# Arduino_Shield.net
KiCad netlist of a schematic drawn in EAGLE
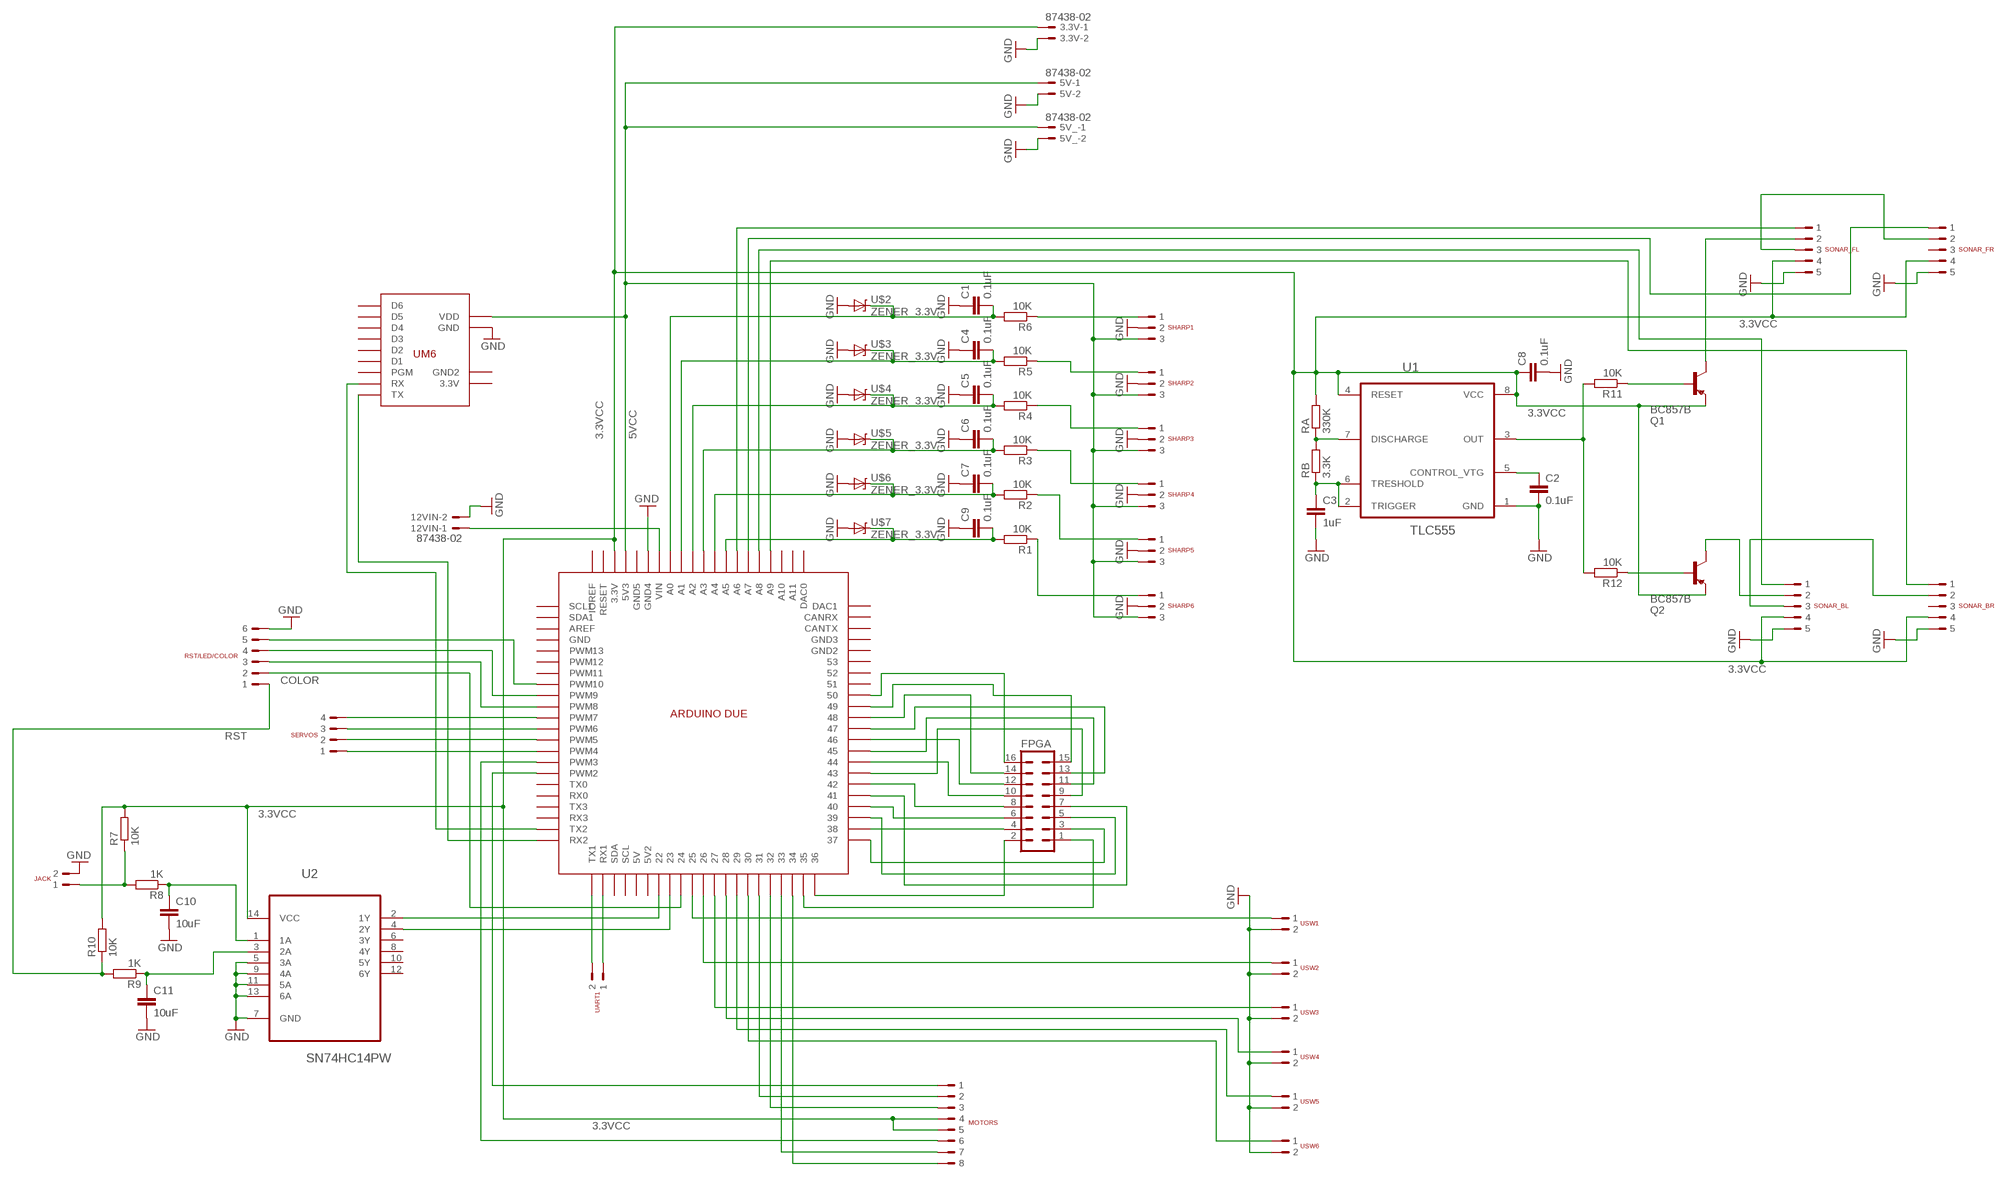
[diagram p0: schematic, sheet 1]

(export (version "E")
  (design (tool "Eeschema 10.0.6"))
  (components
    (comp (ref "3.3V")
      (value "87438-02")
      (footprint "eagle-import:87438-02")
      (libsource (lib "eagle-import") (part "87438-02"))
    )
    (comp (ref "5V")
      (value "87438-02")
      (footprint "eagle-import:87438-02")
      (libsource (lib "eagle-import") (part "87438-02"))
    )
    (comp (ref "5V_")
      (value "87438-02")
      (footprint "eagle-import:87438-02")
      (libsource (lib "eagle-import") (part "87438-02"))
    )
    (comp (ref "12VIN")
      (value "87438-02")
      (footprint "eagle-import:87438-02")
      (libsource (lib "eagle-import") (part "87438-02"))
    )
    (comp (ref "C1")
      (value "0.1uF")
      (footprint "eagle-import:C0603")
      (libsource (lib "eagle-import") (part "C-EUC0603"))
    )
    (comp (ref "C2")
      (value "0.1uF")
      (footprint "eagle-import:C0603")
      (libsource (lib "eagle-import") (part "C-EUC0603"))
    )
    (comp (ref "C3")
      (value "1uF")
      (footprint "eagle-import:C0603")
      (libsource (lib "eagle-import") (part "C-EUC0603"))
    )
    (comp (ref "C4")
      (value "0.1uF")
      (footprint "eagle-import:C0603")
      (libsource (lib "eagle-import") (part "C-EUC0603"))
    )
    (comp (ref "C5")
      (value "0.1uF")
      (footprint "eagle-import:C0603")
      (libsource (lib "eagle-import") (part "C-EUC0603"))
    )
    (comp (ref "C6")
      (value "0.1uF")
      (footprint "eagle-import:C0603")
      (libsource (lib "eagle-import") (part "C-EUC0603"))
    )
    (comp (ref "C7")
      (value "0.1uF")
      (footprint "eagle-import:C0603")
      (libsource (lib "eagle-import") (part "C-EUC0603"))
    )
    (comp (ref "C8")
      (value "0.1uF")
      (footprint "eagle-import:C0603")
      (libsource (lib "eagle-import") (part "C-EUC0603"))
    )
    (comp (ref "C9")
      (value "0.1uF")
      (footprint "eagle-import:C0603")
      (libsource (lib "eagle-import") (part "C-EUC0603"))
    )
    (comp (ref "C10")
      (value "10uF")
      (footprint "eagle-import:C0603")
      (libsource (lib "eagle-import") (part "C-EUC0603"))
    )
    (comp (ref "C11")
      (value "10uF")
      (footprint "eagle-import:C0603")
      (libsource (lib "eagle-import") (part "C-EUC0603"))
    )
    (comp (ref "FPGA")
      (value "ML16")
      (footprint "eagle-import:ML16")
      (libsource (lib "eagle-import") (part "ML16"))
    )
    (comp (ref "JACK")
      (value "87437-0243")
      (footprint "eagle-import:87437-0243")
      (libsource (lib "eagle-import") (part "87437-0243"))
    )
    (comp (ref "MOTORS")
      (value "87437-0843")
      (footprint "eagle-import:87437-0843")
      (libsource (lib "eagle-import") (part "87437-0843"))
    )
    (comp (ref "Q1")
      (value "BC857B")
      (footprint "eagle-import:SOT23")
      (libsource (lib "eagle-import") (part "-?SOT23MMBTA56"))
    )
    (comp (ref "Q2")
      (value "BC857B")
      (footprint "eagle-import:SOT23")
      (libsource (lib "eagle-import") (part "-?SOT23MMBTA56"))
    )
    (comp (ref "R1")
      (value "10K")
      (footprint "eagle-import:R0603")
      (libsource (lib "eagle-import") (part "R-EU_R0603"))
    )
    (comp (ref "R2")
      (value "10K")
      (footprint "eagle-import:R0603")
      (libsource (lib "eagle-import") (part "R-EU_R0603"))
    )
    (comp (ref "R3")
      (value "10K")
      (footprint "eagle-import:R0603")
      (libsource (lib "eagle-import") (part "R-EU_R0603"))
    )
    (comp (ref "R4")
      (value "10K")
      (footprint "eagle-import:R0603")
      (libsource (lib "eagle-import") (part "R-EU_R0603"))
    )
    (comp (ref "R5")
      (value "10K")
      (footprint "eagle-import:R0603")
      (libsource (lib "eagle-import") (part "R-EU_R0603"))
    )
    (comp (ref "R6")
      (value "10K")
      (footprint "eagle-import:R0603")
      (libsource (lib "eagle-import") (part "R-EU_R0603"))
    )
    (comp (ref "R7")
      (value "10K")
      (footprint "eagle-import:R0603")
      (libsource (lib "eagle-import") (part "R-EU_R0603"))
    )
    (comp (ref "R8")
      (value "1K")
      (footprint "eagle-import:R0603")
      (libsource (lib "eagle-import") (part "R-EU_R0603"))
    )
    (comp (ref "R9")
      (value "1K")
      (footprint "eagle-import:R0603")
      (libsource (lib "eagle-import") (part "R-EU_R0603"))
    )
    (comp (ref "R10")
      (value "10K")
      (footprint "eagle-import:R0603")
      (libsource (lib "eagle-import") (part "R-EU_R0603"))
    )
    (comp (ref "R11")
      (value "10K")
      (footprint "eagle-import:R0603")
      (libsource (lib "eagle-import") (part "R-EU_R0603"))
    )
    (comp (ref "R12")
      (value "10K")
      (footprint "eagle-import:R0603")
      (libsource (lib "eagle-import") (part "R-EU_R0603"))
    )
    (comp (ref "RA")
      (value "330K")
      (footprint "eagle-import:R0603")
      (libsource (lib "eagle-import") (part "R-EU_R0603"))
    )
    (comp (ref "RB")
      (value "3.3K")
      (footprint "eagle-import:R0603")
      (libsource (lib "eagle-import") (part "R-EU_R0603"))
    )
    (comp (ref "RST/LED/COLOR")
      (value "87437-0643")
      (footprint "eagle-import:87437-0643")
      (libsource (lib "eagle-import") (part "87437-0643"))
    )
    (comp (ref "SERVOS")
      (value "87437-0443")
      (footprint "eagle-import:87437-0443")
      (libsource (lib "eagle-import") (part "87437-0443"))
    )
    (comp (ref "SHARP1")
      (value "87437-0343")
      (footprint "eagle-import:87437-0343")
      (libsource (lib "eagle-import") (part "87437-0343"))
    )
    (comp (ref "SHARP2")
      (value "87437-0343")
      (footprint "eagle-import:87437-0343")
      (libsource (lib "eagle-import") (part "87437-0343"))
    )
    (comp (ref "SHARP3")
      (value "87437-0343")
      (footprint "eagle-import:87437-0343")
      (libsource (lib "eagle-import") (part "87437-0343"))
    )
    (comp (ref "SHARP4")
      (value "87437-0343")
      (footprint "eagle-import:87437-0343")
      (libsource (lib "eagle-import") (part "87437-0343"))
    )
    (comp (ref "SHARP5")
      (value "87437-0343")
      (footprint "eagle-import:87437-0343")
      (libsource (lib "eagle-import") (part "87437-0343"))
    )
    (comp (ref "SHARP6")
      (value "87437-0343")
      (footprint "eagle-import:87437-0343")
      (libsource (lib "eagle-import") (part "87437-0343"))
    )
    (comp (ref "SONAR_BL")
      (value "87437-0543")
      (footprint "eagle-import:87437-0543")
      (libsource (lib "eagle-import") (part "87437-0543"))
    )
    (comp (ref "SONAR_BR")
      (value "87437-0543")
      (footprint "eagle-import:87437-0543")
      (libsource (lib "eagle-import") (part "87437-0543"))
    )
    (comp (ref "SONAR_FL")
      (value "87437-0543")
      (footprint "eagle-import:87437-0543")
      (libsource (lib "eagle-import") (part "87437-0543"))
    )
    (comp (ref "SONAR_FR")
      (value "87437-0543")
      (footprint "eagle-import:87437-0543")
      (libsource (lib "eagle-import") (part "87437-0543"))
    )
    (comp (ref "U$1")
      (value "ARDUINO-DUE")
      (footprint "eagle-import:ARDUINO-DUE")
      (libsource (lib "eagle-import") (part "ARDUINO-DUE"))
    )
    (comp (ref "U$2")
      (value "ZENER_3.3V")
      (footprint "eagle-import:SOD-323")
      (libsource (lib "eagle-import") (part "DIODE-ZENER-BZT52"))
    )
    (comp (ref "U$3")
      (value "ZENER_3.3V")
      (footprint "eagle-import:SOD-323")
      (libsource (lib "eagle-import") (part "DIODE-ZENER-BZT52"))
    )
    (comp (ref "U$4")
      (value "ZENER_3.3V")
      (footprint "eagle-import:SOD-323")
      (libsource (lib "eagle-import") (part "DIODE-ZENER-BZT52"))
    )
    (comp (ref "U$5")
      (value "ZENER_3.3V")
      (footprint "eagle-import:SOD-323")
      (libsource (lib "eagle-import") (part "DIODE-ZENER-BZT52"))
    )
    (comp (ref "U$6")
      (value "ZENER_3.3V")
      (footprint "eagle-import:SOD-323")
      (libsource (lib "eagle-import") (part "DIODE-ZENER-BZT52"))
    )
    (comp (ref "U$7")
      (value "ZENER_3.3V")
      (footprint "eagle-import:SOD-323")
      (libsource (lib "eagle-import") (part "DIODE-ZENER-BZT52"))
    )
    (comp (ref "U1")
      (value "TLC555")
      (footprint "eagle-import:SOIC127P600X175-8N")
      (fields (field (name "MPN") "LM555CM"))
      (libsource (lib "eagle-import") (part "LM555CM"))
    )
    (comp (ref "U2")
      (value "SN74HC14PW")
      (footprint "eagle-import:SOP65P640X120-14N")
      (libsource (lib "eagle-import") (part "SN74HC14PW"))
    )
    (comp (ref "UART1")
      (value "87437-0243")
      (footprint "eagle-import:87437-0243")
      (libsource (lib "eagle-import") (part "87437-0243"))
    )
    (comp (ref "UM6")
      (value "UM6")
      (footprint "eagle-import:UM6")
      (libsource (lib "eagle-import") (part "UM6"))
    )
    (comp (ref "USW1")
      (value "87437-0243")
      (footprint "eagle-import:87437-0243")
      (libsource (lib "eagle-import") (part "87437-0243"))
    )
    (comp (ref "USW2")
      (value "87437-0243")
      (footprint "eagle-import:87437-0243")
      (libsource (lib "eagle-import") (part "87437-0243"))
    )
    (comp (ref "USW3")
      (value "87437-0243")
      (footprint "eagle-import:87437-0243")
      (libsource (lib "eagle-import") (part "87437-0243"))
    )
    (comp (ref "USW4")
      (value "87437-0243")
      (footprint "eagle-import:87437-0243")
      (libsource (lib "eagle-import") (part "87437-0243"))
    )
    (comp (ref "USW5")
      (value "87437-0243")
      (footprint "eagle-import:87437-0243")
      (libsource (lib "eagle-import") (part "87437-0243"))
    )
    (comp (ref "USW6")
      (value "87437-0243")
      (footprint "eagle-import:87437-0243")
      (libsource (lib "eagle-import") (part "87437-0243"))
    )
  )
  (nets
    (net (code "1") (name "/3.3VCC") (class "Default")
      (node (ref "3.3V") (pin "1") (pinfunction "S_1") (pintype "passive"))
      (node (ref "C8") (pin "1") (pinfunction "1_1") (pintype "passive"))
      (node (ref "MOTORS") (pin "P$4") (pinfunction "4_P$4") (pintype "bidirectional"))
      (node (ref "MOTORS") (pin "P$5") (pinfunction "5_P$5") (pintype "bidirectional"))
      (node (ref "Q1") (pin "2") (pinfunction "E_2") (pintype "passive"))
      (node (ref "Q2") (pin "2") (pinfunction "E_2") (pintype "passive"))
      (node (ref "R10") (pin "2") (pinfunction "2_2") (pintype "passive"))
      (node (ref "R7") (pin "2") (pinfunction "2_2") (pintype "passive"))
      (node (ref "RA") (pin "2") (pinfunction "2_2") (pintype "passive"))
      (node (ref "SONAR_BL") (pin "P$4") (pinfunction "4_P$4") (pintype "bidirectional"))
      (node (ref "SONAR_BR") (pin "P$4") (pinfunction "4_P$4") (pintype "bidirectional"))
      (node (ref "SONAR_FL") (pin "P$4") (pinfunction "4_P$4") (pintype "bidirectional"))
      (node (ref "SONAR_FR") (pin "P$4") (pinfunction "4_P$4") (pintype "bidirectional"))
      (node (ref "U$1") (pin "3.3V") (pinfunction "3.3V_3.3V") (pintype "bidirectional"))
      (node (ref "U1") (pin "4") (pinfunction "RESET_4") (pintype "input"))
      (node (ref "U1") (pin "8") (pinfunction "VCC_8") (pintype "power_in"))
      (node (ref "U2") (pin "14") (pinfunction "VCC_14") (pintype "power_in"))
    )
    (net (code "2") (name "/5VCC") (class "Default")
      (node (ref "5V") (pin "1") (pinfunction "S_1") (pintype "passive"))
      (node (ref "5V_") (pin "1") (pinfunction "S_1") (pintype "passive"))
      (node (ref "SHARP1") (pin "P$3") (pinfunction "3_P$3") (pintype "bidirectional"))
      (node (ref "SHARP2") (pin "P$3") (pinfunction "3_P$3") (pintype "bidirectional"))
      (node (ref "SHARP3") (pin "P$3") (pinfunction "3_P$3") (pintype "bidirectional"))
      (node (ref "SHARP4") (pin "P$3") (pinfunction "3_P$3") (pintype "bidirectional"))
      (node (ref "SHARP5") (pin "P$3") (pinfunction "3_P$3") (pintype "bidirectional"))
      (node (ref "SHARP6") (pin "P$3") (pinfunction "3_P$3") (pintype "bidirectional"))
      (node (ref "U$1") (pin "5V3") (pinfunction "5V3_5V3") (pintype "bidirectional"))
      (node (ref "UM6") (pin "P$10") (pinfunction "VDD_P$10") (pintype "bidirectional"))
    )
    (net (code "3") (name "/COLOR") (class "Default")
      (node (ref "RST/LED/COLOR") (pin "P$2") (pinfunction "2_P$2") (pintype "bidirectional"))
      (node (ref "U$1") (pin "24") (pinfunction "24_24") (pintype "bidirectional"))
    )
    (net (code "4") (name "/RST") (class "Default")
      (node (ref "R10") (pin "1") (pinfunction "1_1") (pintype "passive"))
      (node (ref "R9") (pin "2") (pinfunction "2_2") (pintype "passive"))
      (node (ref "RST/LED/COLOR") (pin "P$1") (pinfunction "1_P$1") (pintype "bidirectional"))
    )
    (net (code "5") (name "GND") (class "Default")
      (node (ref "12VIN") (pin "2") (pinfunction "S_2") (pintype "passive"))
      (node (ref "3.3V") (pin "2") (pinfunction "S_2") (pintype "passive"))
      (node (ref "5V") (pin "2") (pinfunction "S_2") (pintype "passive"))
      (node (ref "5V_") (pin "2") (pinfunction "S_2") (pintype "passive"))
      (node (ref "C1") (pin "1") (pinfunction "1_1") (pintype "passive"))
      (node (ref "C10") (pin "2") (pinfunction "2_2") (pintype "passive"))
      (node (ref "C11") (pin "2") (pinfunction "2_2") (pintype "passive"))
      (node (ref "C2") (pin "2") (pinfunction "2_2") (pintype "passive"))
      (node (ref "C3") (pin "2") (pinfunction "2_2") (pintype "passive"))
      (node (ref "C4") (pin "1") (pinfunction "1_1") (pintype "passive"))
      (node (ref "C5") (pin "1") (pinfunction "1_1") (pintype "passive"))
      (node (ref "C6") (pin "1") (pinfunction "1_1") (pintype "passive"))
      (node (ref "C7") (pin "1") (pinfunction "1_1") (pintype "passive"))
      (node (ref "C8") (pin "2") (pinfunction "2_2") (pintype "passive"))
      (node (ref "C9") (pin "1") (pinfunction "1_1") (pintype "passive"))
      (node (ref "JACK") (pin "P$2") (pinfunction "2_P$2") (pintype "bidirectional"))
      (node (ref "RST/LED/COLOR") (pin "P$6") (pinfunction "6_P$6") (pintype "bidirectional"))
      (node (ref "SHARP1") (pin "P$2") (pinfunction "2_P$2") (pintype "bidirectional"))
      (node (ref "SHARP2") (pin "P$2") (pinfunction "2_P$2") (pintype "bidirectional"))
      (node (ref "SHARP3") (pin "P$2") (pinfunction "2_P$2") (pintype "bidirectional"))
      (node (ref "SHARP4") (pin "P$2") (pinfunction "2_P$2") (pintype "bidirectional"))
      (node (ref "SHARP5") (pin "P$2") (pinfunction "2_P$2") (pintype "bidirectional"))
      (node (ref "SHARP6") (pin "P$2") (pinfunction "2_P$2") (pintype "bidirectional"))
      (node (ref "SONAR_BL") (pin "P$5") (pinfunction "5_P$5") (pintype "bidirectional"))
      (node (ref "SONAR_BR") (pin "P$5") (pinfunction "5_P$5") (pintype "bidirectional"))
      (node (ref "SONAR_FL") (pin "P$5") (pinfunction "5_P$5") (pintype "bidirectional"))
      (node (ref "SONAR_FR") (pin "P$5") (pinfunction "5_P$5") (pintype "bidirectional"))
      (node (ref "U$1") (pin "GND4") (pinfunction "GND4_GND4") (pintype "bidirectional"))
      (node (ref "U$2") (pin "2") (pinfunction "A_2") (pintype "passive"))
      (node (ref "U$3") (pin "2") (pinfunction "A_2") (pintype "passive"))
      (node (ref "U$4") (pin "2") (pinfunction "A_2") (pintype "passive"))
      (node (ref "U$5") (pin "2") (pinfunction "A_2") (pintype "passive"))
      (node (ref "U$6") (pin "2") (pinfunction "A_2") (pintype "passive"))
      (node (ref "U$7") (pin "2") (pinfunction "A_2") (pintype "passive"))
      (node (ref "U1") (pin "1") (pinfunction "GND_1") (pintype "passive"))
      (node (ref "U2") (pin "11") (pinfunction "5A_11") (pintype "input"))
      (node (ref "U2") (pin "13") (pinfunction "6A_13") (pintype "input"))
      (node (ref "U2") (pin "5") (pinfunction "3A_5") (pintype "input"))
      (node (ref "U2") (pin "7") (pinfunction "GND_7") (pintype "passive"))
      (node (ref "U2") (pin "9") (pinfunction "4A_9") (pintype "input"))
      (node (ref "UM6") (pin "P$11") (pinfunction "GND_P$11") (pintype "bidirectional"))
      (node (ref "USW1") (pin "P$2") (pinfunction "2_P$2") (pintype "bidirectional"))
      (node (ref "USW2") (pin "P$2") (pinfunction "2_P$2") (pintype "bidirectional"))
      (node (ref "USW3") (pin "P$2") (pinfunction "2_P$2") (pintype "bidirectional"))
      (node (ref "USW4") (pin "P$2") (pinfunction "2_P$2") (pintype "bidirectional"))
      (node (ref "USW5") (pin "P$2") (pinfunction "2_P$2") (pintype "bidirectional"))
      (node (ref "USW6") (pin "P$2") (pinfunction "2_P$2") (pintype "bidirectional"))
    )
    (net (code "6") (name "Net-(12VINA-S)") (class "Default")
      (node (ref "12VIN") (pin "1") (pinfunction "S_1") (pintype "passive"))
      (node (ref "U$1") (pin "VIN") (pinfunction "VIN_VIN") (pintype "bidirectional"))
    )
    (net (code "7") (name "Net-(FPGA-Pad1)") (class "Default")
      (node (ref "FPGA") (pin "1") (pinfunction "1_1") (pintype "passive"))
      (node (ref "U$1") (pin "35") (pinfunction "35_35") (pintype "bidirectional"))
    )
    (net (code "8") (name "Net-(FPGA-Pad2)") (class "Default")
      (node (ref "FPGA") (pin "2") (pinfunction "2_2") (pintype "passive"))
      (node (ref "U$1") (pin "36") (pinfunction "36_36") (pintype "bidirectional"))
    )
    (net (code "9") (name "Net-(FPGA-Pad3)") (class "Default")
      (node (ref "FPGA") (pin "3") (pinfunction "3_3") (pintype "passive"))
      (node (ref "U$1") (pin "37") (pinfunction "37_37") (pintype "bidirectional"))
    )
    (net (code "10") (name "Net-(FPGA-Pad4)") (class "Default")
      (node (ref "FPGA") (pin "4") (pinfunction "4_4") (pintype "passive"))
      (node (ref "U$1") (pin "38") (pinfunction "38_38") (pintype "bidirectional"))
    )
    (net (code "11") (name "Net-(FPGA-Pad5)") (class "Default")
      (node (ref "FPGA") (pin "5") (pinfunction "5_5") (pintype "passive"))
      (node (ref "U$1") (pin "39") (pinfunction "39_39") (pintype "bidirectional"))
    )
    (net (code "12") (name "Net-(FPGA-Pad6)") (class "Default")
      (node (ref "FPGA") (pin "6") (pinfunction "6_6") (pintype "passive"))
      (node (ref "U$1") (pin "40") (pinfunction "40_40") (pintype "bidirectional"))
    )
    (net (code "13") (name "Net-(FPGA-Pad7)") (class "Default")
      (node (ref "FPGA") (pin "7") (pinfunction "7_7") (pintype "passive"))
      (node (ref "U$1") (pin "41") (pinfunction "41_41") (pintype "bidirectional"))
    )
    (net (code "14") (name "Net-(FPGA-Pad8)") (class "Default")
      (node (ref "FPGA") (pin "8") (pinfunction "8_8") (pintype "passive"))
      (node (ref "U$1") (pin "42") (pinfunction "42_42") (pintype "bidirectional"))
    )
    (net (code "15") (name "Net-(FPGA-Pad9)") (class "Default")
      (node (ref "FPGA") (pin "9") (pinfunction "9_9") (pintype "passive"))
      (node (ref "U$1") (pin "43") (pinfunction "43_43") (pintype "bidirectional"))
    )
    (net (code "16") (name "Net-(FPGA-Pad10)") (class "Default")
      (node (ref "FPGA") (pin "10") (pinfunction "10_10") (pintype "passive"))
      (node (ref "U$1") (pin "44") (pinfunction "44_44") (pintype "bidirectional"))
    )
    (net (code "17") (name "Net-(FPGA-Pad11)") (class "Default")
      (node (ref "FPGA") (pin "11") (pinfunction "11_11") (pintype "passive"))
      (node (ref "U$1") (pin "45") (pinfunction "45_45") (pintype "bidirectional"))
    )
    (net (code "18") (name "Net-(FPGA-Pad12)") (class "Default")
      (node (ref "FPGA") (pin "12") (pinfunction "12_12") (pintype "passive"))
      (node (ref "U$1") (pin "46") (pinfunction "46_46") (pintype "bidirectional"))
    )
    (net (code "19") (name "Net-(FPGA-Pad13)") (class "Default")
      (node (ref "FPGA") (pin "13") (pinfunction "13_13") (pintype "passive"))
      (node (ref "U$1") (pin "47") (pinfunction "47_47") (pintype "bidirectional"))
    )
    (net (code "20") (name "Net-(FPGA-Pad14)") (class "Default")
      (node (ref "FPGA") (pin "14") (pinfunction "14_14") (pintype "passive"))
      (node (ref "U$1") (pin "48") (pinfunction "48_48") (pintype "bidirectional"))
    )
    (net (code "21") (name "Net-(FPGA-Pad15)") (class "Default")
      (node (ref "FPGA") (pin "15") (pinfunction "15_15") (pintype "passive"))
      (node (ref "U$1") (pin "49") (pinfunction "49_49") (pintype "bidirectional"))
    )
    (net (code "22") (name "Net-(FPGA-Pad16)") (class "Default")
      (node (ref "FPGA") (pin "16") (pinfunction "16_16") (pintype "passive"))
      (node (ref "U$1") (pin "50") (pinfunction "50_50") (pintype "bidirectional"))
    )
    (net (code "23") (name "Net-(JACK-1)") (class "Default")
      (node (ref "JACK") (pin "P$1") (pinfunction "1_P$1") (pintype "bidirectional"))
      (node (ref "R7") (pin "1") (pinfunction "1_1") (pintype "passive"))
      (node (ref "R8") (pin "2") (pinfunction "2_2") (pintype "passive"))
    )
    (net (code "24") (name "Net-(MOTORS-1)") (class "Default")
      (node (ref "MOTORS") (pin "P$1") (pinfunction "1_P$1") (pintype "bidirectional"))
      (node (ref "U$1") (pin "PWM2") (pinfunction "PWM2_PWM2") (pintype "bidirectional"))
    )
    (net (code "25") (name "Net-(MOTORS-2)") (class "Default")
      (node (ref "MOTORS") (pin "P$2") (pinfunction "2_P$2") (pintype "bidirectional"))
      (node (ref "U$1") (pin "31") (pinfunction "31_31") (pintype "bidirectional"))
    )
    (net (code "26") (name "Net-(MOTORS-3)") (class "Default")
      (node (ref "MOTORS") (pin "P$3") (pinfunction "3_P$3") (pintype "bidirectional"))
      (node (ref "U$1") (pin "32") (pinfunction "32_32") (pintype "bidirectional"))
    )
    (net (code "27") (name "Net-(MOTORS-6)") (class "Default")
      (node (ref "MOTORS") (pin "P$6") (pinfunction "6_P$6") (pintype "bidirectional"))
      (node (ref "U$1") (pin "PWM3") (pinfunction "PWM3_PWM3") (pintype "bidirectional"))
    )
    (net (code "28") (name "Net-(MOTORS-7)") (class "Default")
      (node (ref "MOTORS") (pin "P$7") (pinfunction "7_P$7") (pintype "bidirectional"))
      (node (ref "U$1") (pin "33") (pinfunction "33_33") (pintype "bidirectional"))
    )
    (net (code "29") (name "Net-(MOTORS-8)") (class "Default")
      (node (ref "MOTORS") (pin "P$8") (pinfunction "8_P$8") (pintype "bidirectional"))
      (node (ref "U$1") (pin "34") (pinfunction "34_34") (pintype "bidirectional"))
    )
    (net (code "30") (name "Net-(Q1-B)") (class "Default")
      (node (ref "Q1") (pin "1") (pinfunction "B_1") (pintype "passive"))
      (node (ref "R11") (pin "1") (pinfunction "1_1") (pintype "passive"))
    )
    (net (code "31") (name "Net-(Q1-C)") (class "Default")
      (node (ref "Q1") (pin "3") (pinfunction "C_3") (pintype "passive"))
      (node (ref "SONAR_FL") (pin "P$2") (pinfunction "2_P$2") (pintype "bidirectional"))
    )
    (net (code "32") (name "Net-(Q2-B)") (class "Default")
      (node (ref "Q2") (pin "1") (pinfunction "B_1") (pintype "passive"))
      (node (ref "R12") (pin "1") (pinfunction "1_1") (pintype "passive"))
    )
    (net (code "33") (name "Net-(Q2-C)") (class "Default")
      (node (ref "Q2") (pin "3") (pinfunction "C_3") (pintype "passive"))
      (node (ref "SONAR_BL") (pin "P$2") (pinfunction "2_P$2") (pintype "bidirectional"))
    )
    (net (code "34") (name "Net-(RST/LED/COLOR-3)") (class "Default")
      (node (ref "RST/LED/COLOR") (pin "P$3") (pinfunction "3_P$3") (pintype "bidirectional"))
      (node (ref "U$1") (pin "PWM8") (pinfunction "PWM8_PWM8") (pintype "bidirectional"))
    )
    (net (code "35") (name "Net-(RST/LED/COLOR-4)") (class "Default")
      (node (ref "RST/LED/COLOR") (pin "P$4") (pinfunction "4_P$4") (pintype "bidirectional"))
      (node (ref "U$1") (pin "PWM9") (pinfunction "PWM9_PWM9") (pintype "bidirectional"))
    )
    (net (code "36") (name "Net-(RST/LED/COLOR-5)") (class "Default")
      (node (ref "RST/LED/COLOR") (pin "P$5") (pinfunction "5_P$5") (pintype "bidirectional"))
      (node (ref "U$1") (pin "PWM10") (pinfunction "PWM10_PWM10") (pintype "bidirectional"))
    )
    (net (code "37") (name "Net-(SERVOS-1)") (class "Default")
      (node (ref "SERVOS") (pin "P$1") (pinfunction "1_P$1") (pintype "bidirectional"))
      (node (ref "U$1") (pin "PWM4") (pinfunction "PWM4_PWM4") (pintype "bidirectional"))
    )
    (net (code "38") (name "Net-(SERVOS-2)") (class "Default")
      (node (ref "SERVOS") (pin "P$2") (pinfunction "2_P$2") (pintype "bidirectional"))
      (node (ref "U$1") (pin "PWM5") (pinfunction "PWM5_PWM5") (pintype "bidirectional"))
    )
    (net (code "39") (name "Net-(SERVOS-3)") (class "Default")
      (node (ref "SERVOS") (pin "P$3") (pinfunction "3_P$3") (pintype "bidirectional"))
      (node (ref "U$1") (pin "PWM6") (pinfunction "PWM6_PWM6") (pintype "bidirectional"))
    )
    (net (code "40") (name "Net-(SERVOS-4)") (class "Default")
      (node (ref "SERVOS") (pin "P$4") (pinfunction "4_P$4") (pintype "bidirectional"))
      (node (ref "U$1") (pin "PWM7") (pinfunction "PWM7_PWM7") (pintype "bidirectional"))
    )
    (net (code "41") (name "Net-(SHARP1-1)") (class "Default")
      (node (ref "R6") (pin "1") (pinfunction "1_1") (pintype "passive"))
      (node (ref "SHARP1") (pin "P$1") (pinfunction "1_P$1") (pintype "bidirectional"))
    )
    (net (code "42") (name "Net-(SHARP2-1)") (class "Default")
      (node (ref "R5") (pin "1") (pinfunction "1_1") (pintype "passive"))
      (node (ref "SHARP2") (pin "P$1") (pinfunction "1_P$1") (pintype "bidirectional"))
    )
    (net (code "43") (name "Net-(SHARP3-1)") (class "Default")
      (node (ref "R4") (pin "1") (pinfunction "1_1") (pintype "passive"))
      (node (ref "SHARP3") (pin "P$1") (pinfunction "1_P$1") (pintype "bidirectional"))
    )
    (net (code "44") (name "Net-(SHARP4-1)") (class "Default")
      (node (ref "R3") (pin "1") (pinfunction "1_1") (pintype "passive"))
      (node (ref "SHARP4") (pin "P$1") (pinfunction "1_P$1") (pintype "bidirectional"))
    )
    (net (code "45") (name "Net-(SHARP5-1)") (class "Default")
      (node (ref "R2") (pin "1") (pinfunction "1_1") (pintype "passive"))
      (node (ref "SHARP5") (pin "P$1") (pinfunction "1_P$1") (pintype "bidirectional"))
    )
    (net (code "46") (name "Net-(SHARP6-1)") (class "Default")
      (node (ref "R1") (pin "1") (pinfunction "1_1") (pintype "passive"))
      (node (ref "SHARP6") (pin "P$1") (pinfunction "1_P$1") (pintype "bidirectional"))
    )
    (net (code "47") (name "Net-(SONAR_BL-1)") (class "Default")
      (node (ref "SONAR_BL") (pin "P$1") (pinfunction "1_P$1") (pintype "bidirectional"))
      (node (ref "U$1") (pin "A8") (pinfunction "A8_A8") (pintype "bidirectional"))
    )
    (net (code "48") (name "Net-(SONAR_BL-3)") (class "Default")
      (node (ref "SONAR_BL") (pin "P$3") (pinfunction "3_P$3") (pintype "bidirectional"))
      (node (ref "SONAR_BR") (pin "P$2") (pinfunction "2_P$2") (pintype "bidirectional"))
    )
    (net (code "49") (name "Net-(SONAR_BR-1)") (class "Default")
      (node (ref "SONAR_BR") (pin "P$1") (pinfunction "1_P$1") (pintype "bidirectional"))
      (node (ref "U$1") (pin "A9") (pinfunction "A9_A9") (pintype "bidirectional"))
    )
    (net (code "50") (name "Net-(SONAR_FL-1)") (class "Default")
      (node (ref "SONAR_FL") (pin "P$1") (pinfunction "1_P$1") (pintype "bidirectional"))
      (node (ref "U$1") (pin "A6") (pinfunction "A6_A6") (pintype "bidirectional"))
    )
    (net (code "51") (name "Net-(SONAR_FL-3)") (class "Default")
      (node (ref "SONAR_FL") (pin "P$3") (pinfunction "3_P$3") (pintype "bidirectional"))
      (node (ref "SONAR_FR") (pin "P$2") (pinfunction "2_P$2") (pintype "bidirectional"))
    )
    (net (code "52") (name "Net-(SONAR_FR-1)") (class "Default")
      (node (ref "SONAR_FR") (pin "P$1") (pinfunction "1_P$1") (pintype "bidirectional"))
      (node (ref "U$1") (pin "A7") (pinfunction "A7_A7") (pintype "bidirectional"))
    )
    (net (code "53") (name "Net-(U$2-C)") (class "Default")
      (node (ref "C1") (pin "2") (pinfunction "2_2") (pintype "passive"))
      (node (ref "R6") (pin "2") (pinfunction "2_2") (pintype "passive"))
      (node (ref "U$1") (pin "A0") (pinfunction "A0_A0") (pintype "bidirectional"))
      (node (ref "U$2") (pin "1") (pinfunction "C_1") (pintype "passive"))
    )
    (net (code "54") (name "Net-(U$3-C)") (class "Default")
      (node (ref "C4") (pin "2") (pinfunction "2_2") (pintype "passive"))
      (node (ref "R5") (pin "2") (pinfunction "2_2") (pintype "passive"))
      (node (ref "U$1") (pin "A1") (pinfunction "A1_A1") (pintype "bidirectional"))
      (node (ref "U$3") (pin "1") (pinfunction "C_1") (pintype "passive"))
    )
    (net (code "55") (name "Net-(U$4-C)") (class "Default")
      (node (ref "C5") (pin "2") (pinfunction "2_2") (pintype "passive"))
      (node (ref "R4") (pin "2") (pinfunction "2_2") (pintype "passive"))
      (node (ref "U$1") (pin "A2") (pinfunction "A2_A2") (pintype "bidirectional"))
      (node (ref "U$4") (pin "1") (pinfunction "C_1") (pintype "passive"))
    )
    (net (code "56") (name "Net-(U$5-C)") (class "Default")
      (node (ref "C6") (pin "2") (pinfunction "2_2") (pintype "passive"))
      (node (ref "R3") (pin "2") (pinfunction "2_2") (pintype "passive"))
      (node (ref "U$1") (pin "A3") (pinfunction "A3_A3") (pintype "bidirectional"))
      (node (ref "U$5") (pin "1") (pinfunction "C_1") (pintype "passive"))
    )
    (net (code "57") (name "Net-(U$6-C)") (class "Default")
      (node (ref "C7") (pin "2") (pinfunction "2_2") (pintype "passive"))
      (node (ref "R2") (pin "2") (pinfunction "2_2") (pintype "passive"))
      (node (ref "U$1") (pin "A4") (pinfunction "A4_A4") (pintype "bidirectional"))
      (node (ref "U$6") (pin "1") (pinfunction "C_1") (pintype "passive"))
    )
    (net (code "58") (name "Net-(U$7-C)") (class "Default")
      (node (ref "C9") (pin "2") (pinfunction "2_2") (pintype "passive"))
      (node (ref "R1") (pin "2") (pinfunction "2_2") (pintype "passive"))
      (node (ref "U$1") (pin "A5") (pinfunction "A5_A5") (pintype "bidirectional"))
      (node (ref "U$7") (pin "1") (pinfunction "C_1") (pintype "passive"))
    )
    (net (code "59") (name "Net-(U1-CONTROL_VTG)") (class "Default")
      (node (ref "C2") (pin "1") (pinfunction "1_1") (pintype "passive"))
      (node (ref "U1") (pin "5") (pinfunction "CONTROL_VTG_5") (pintype "input"))
    )
    (net (code "60") (name "Net-(U1-DISCHARGE)") (class "Default")
      (node (ref "RA") (pin "1") (pinfunction "1_1") (pintype "passive"))
      (node (ref "RB") (pin "2") (pinfunction "2_2") (pintype "passive"))
      (node (ref "U1") (pin "7") (pinfunction "DISCHARGE_7") (pintype "input"))
    )
    (net (code "61") (name "Net-(U1-OUT)") (class "Default")
      (node (ref "R11") (pin "2") (pinfunction "2_2") (pintype "passive"))
      (node (ref "R12") (pin "2") (pinfunction "2_2") (pintype "passive"))
      (node (ref "U1") (pin "3") (pinfunction "OUT_3") (pintype "output"))
    )
    (net (code "62") (name "Net-(U1-TRESHOLD)") (class "Default")
      (node (ref "C3") (pin "1") (pinfunction "1_1") (pintype "passive"))
      (node (ref "RB") (pin "1") (pinfunction "1_1") (pintype "passive"))
      (node (ref "U1") (pin "2") (pinfunction "TRIGGER_2") (pintype "input"))
      (node (ref "U1") (pin "6") (pinfunction "TRESHOLD_6") (pintype "input"))
    )
    (net (code "63") (name "Net-(U2-1A)") (class "Default")
      (node (ref "C10") (pin "1") (pinfunction "1_1") (pintype "passive"))
      (node (ref "R8") (pin "1") (pinfunction "1_1") (pintype "passive"))
      (node (ref "U2") (pin "1") (pinfunction "1A_1") (pintype "input"))
    )
    (net (code "64") (name "Net-(U2-1Y)") (class "Default")
      (node (ref "U$1") (pin "22") (pinfunction "22_22") (pintype "bidirectional"))
      (node (ref "U2") (pin "2") (pinfunction "1Y_2") (pintype "output"))
    )
    (net (code "65") (name "Net-(U2-2A)") (class "Default")
      (node (ref "C11") (pin "1") (pinfunction "1_1") (pintype "passive"))
      (node (ref "R9") (pin "1") (pinfunction "1_1") (pintype "passive"))
      (node (ref "U2") (pin "3") (pinfunction "2A_3") (pintype "input"))
    )
    (net (code "66") (name "Net-(U2-2Y)") (class "Default")
      (node (ref "U$1") (pin "23") (pinfunction "23_23") (pintype "bidirectional"))
      (node (ref "U2") (pin "4") (pinfunction "2Y_4") (pintype "output"))
    )
    (net (code "67") (name "Net-(UART1-1)") (class "Default")
      (node (ref "U$1") (pin "RX1") (pinfunction "RX1_RX1") (pintype "bidirectional"))
      (node (ref "UART1") (pin "P$1") (pinfunction "1_P$1") (pintype "bidirectional"))
    )
    (net (code "68") (name "Net-(UART1-2)") (class "Default")
      (node (ref "U$1") (pin "TX1") (pinfunction "TX1_TX1") (pintype "bidirectional"))
      (node (ref "UART1") (pin "P$2") (pinfunction "2_P$2") (pintype "bidirectional"))
    )
    (net (code "69") (name "Net-(UM6-RX)") (class "Default")
      (node (ref "U$1") (pin "TX2") (pinfunction "TX2_TX2") (pintype "bidirectional"))
      (node (ref "UM6") (pin "P$2") (pinfunction "RX_P$2") (pintype "bidirectional"))
    )
    (net (code "70") (name "Net-(UM6-TX)") (class "Default")
      (node (ref "U$1") (pin "RX2") (pinfunction "RX2_RX2") (pintype "bidirectional"))
      (node (ref "UM6") (pin "P$1") (pinfunction "TX_P$1") (pintype "bidirectional"))
    )
    (net (code "71") (name "Net-(USW1-1)") (class "Default")
      (node (ref "U$1") (pin "25") (pinfunction "25_25") (pintype "bidirectional"))
      (node (ref "USW1") (pin "P$1") (pinfunction "1_P$1") (pintype "bidirectional"))
    )
    (net (code "72") (name "Net-(USW2-1)") (class "Default")
      (node (ref "U$1") (pin "26") (pinfunction "26_26") (pintype "bidirectional"))
      (node (ref "USW2") (pin "P$1") (pinfunction "1_P$1") (pintype "bidirectional"))
    )
    (net (code "73") (name "Net-(USW3-1)") (class "Default")
      (node (ref "U$1") (pin "27") (pinfunction "27_27") (pintype "bidirectional"))
      (node (ref "USW3") (pin "P$1") (pinfunction "1_P$1") (pintype "bidirectional"))
    )
    (net (code "74") (name "Net-(USW4-1)") (class "Default")
      (node (ref "U$1") (pin "28") (pinfunction "28_28") (pintype "bidirectional"))
      (node (ref "USW4") (pin "P$1") (pinfunction "1_P$1") (pintype "bidirectional"))
    )
    (net (code "75") (name "Net-(USW5-1)") (class "Default")
      (node (ref "U$1") (pin "29") (pinfunction "29_29") (pintype "bidirectional"))
      (node (ref "USW5") (pin "P$1") (pinfunction "1_P$1") (pintype "bidirectional"))
    )
    (net (code "76") (name "Net-(USW6-1)") (class "Default")
      (node (ref "U$1") (pin "30") (pinfunction "30_30") (pintype "bidirectional"))
      (node (ref "USW6") (pin "P$1") (pinfunction "1_P$1") (pintype "bidirectional"))
    )
    (net (code "77") (name "unconnected-(SONAR_BR-3-PadP$3)") (class "Default")
      (node (ref "SONAR_BR") (pin "P$3") (pinfunction "3_P$3") (pintype "bidirectional"))
    )
    (net (code "78") (name "unconnected-(SONAR_FR-3-PadP$3)") (class "Default")
      (node (ref "SONAR_FR") (pin "P$3") (pinfunction "3_P$3") (pintype "bidirectional"))
    )
    (net (code "79") (name "unconnected-(U$1-Pad5V)") (class "Default")
      (node (ref "U$1") (pin "5V") (pinfunction "5V_5V") (pintype "bidirectional"))
    )
    (net (code "80") (name "unconnected-(U$1-Pad5V2)") (class "Default")
      (node (ref "U$1") (pin "5V2") (pinfunction "5V2_5V2") (pintype "bidirectional"))
    )
    (net (code "81") (name "unconnected-(U$1-Pad51)") (class "Default")
      (node (ref "U$1") (pin "51") (pinfunction "51_51") (pintype "bidirectional"))
    )
    (net (code "82") (name "unconnected-(U$1-Pad52)") (class "Default")
      (node (ref "U$1") (pin "52") (pinfunction "52_52") (pintype "bidirectional"))
    )
    (net (code "83") (name "unconnected-(U$1-Pad53)") (class "Default")
      (node (ref "U$1") (pin "53") (pinfunction "53_53") (pintype "bidirectional"))
    )
    (net (code "84") (name "unconnected-(U$1-PadA10)") (class "Default")
      (node (ref "U$1") (pin "A10") (pinfunction "A10_A10") (pintype "bidirectional"))
    )
    (net (code "85") (name "unconnected-(U$1-PadA11)") (class "Default")
      (node (ref "U$1") (pin "A11") (pinfunction "A11_A11") (pintype "bidirectional"))
    )
    (net (code "86") (name "unconnected-(U$1-PadAREF)") (class "Default")
      (node (ref "U$1") (pin "AREF") (pinfunction "AREF_AREF") (pintype "bidirectional"))
    )
    (net (code "87") (name "unconnected-(U$1-PadCANRX)") (class "Default")
      (node (ref "U$1") (pin "CANRX") (pinfunction "CANRX_CANRX") (pintype "bidirectional"))
    )
    (net (code "88") (name "unconnected-(U$1-PadCANTX)") (class "Default")
      (node (ref "U$1") (pin "CANTX") (pinfunction "CANTX_CANTX") (pintype "bidirectional"))
    )
    (net (code "89") (name "unconnected-(U$1-PadDAC0)") (class "Default")
      (node (ref "U$1") (pin "DAC0") (pinfunction "DAC0_DAC0") (pintype "bidirectional"))
    )
    (net (code "90") (name "unconnected-(U$1-PadDAC1)") (class "Default")
      (node (ref "U$1") (pin "DAC1") (pinfunction "DAC1_DAC1") (pintype "bidirectional"))
    )
    (net (code "91") (name "unconnected-(U$1-PadGND)") (class "Default")
      (node (ref "U$1") (pin "GND") (pinfunction "GND_GND") (pintype "bidirectional"))
    )
    (net (code "92") (name "unconnected-(U$1-PadGND2)") (class "Default")
      (node (ref "U$1") (pin "GND2") (pinfunction "GND2_GND2") (pintype "bidirectional"))
    )
    (net (code "93") (name "unconnected-(U$1-PadGND3)") (class "Default")
      (node (ref "U$1") (pin "GND3") (pinfunction "GND3_GND3") (pintype "bidirectional"))
    )
    (net (code "94") (name "unconnected-(U$1-PadGND5)") (class "Default")
      (node (ref "U$1") (pin "GND5") (pinfunction "GND5_GND5") (pintype "bidirectional"))
    )
    (net (code "95") (name "unconnected-(U$1-PadIOREF)") (class "Default")
      (node (ref "U$1") (pin "IOREF") (pinfunction "IOREF_IOREF") (pintype "bidirectional"))
    )
    (net (code "96") (name "unconnected-(U$1-PadPWM11)") (class "Default")
      (node (ref "U$1") (pin "PWM11") (pinfunction "PWM11_PWM11") (pintype "bidirectional"))
    )
    (net (code "97") (name "unconnected-(U$1-PadPWM12)") (class "Default")
      (node (ref "U$1") (pin "PWM12") (pinfunction "PWM12_PWM12") (pintype "bidirectional"))
    )
    (net (code "98") (name "unconnected-(U$1-PadPWM13)") (class "Default")
      (node (ref "U$1") (pin "PWM13") (pinfunction "PWM13_PWM13") (pintype "bidirectional"))
    )
    (net (code "99") (name "unconnected-(U$1-PadRESET)") (class "Default")
      (node (ref "U$1") (pin "RESET") (pinfunction "RESET_RESET") (pintype "bidirectional"))
    )
    (net (code "100") (name "unconnected-(U$1-PadRX0)") (class "Default")
      (node (ref "U$1") (pin "RX0") (pinfunction "RX0_RX0") (pintype "bidirectional"))
    )
    (net (code "101") (name "unconnected-(U$1-PadRX3)") (class "Default")
      (node (ref "U$1") (pin "RX3") (pinfunction "RX3_RX3") (pintype "bidirectional"))
    )
    (net (code "102") (name "unconnected-(U$1-PadSCL)") (class "Default")
      (node (ref "U$1") (pin "SCL") (pinfunction "SCL_SCL") (pintype "bidirectional"))
    )
    (net (code "103") (name "unconnected-(U$1-PadSCL1)") (class "Default")
      (node (ref "U$1") (pin "SCL1") (pinfunction "SCL1_SCL1") (pintype "bidirectional"))
    )
    (net (code "104") (name "unconnected-(U$1-PadSDA)") (class "Default")
      (node (ref "U$1") (pin "SDA") (pinfunction "SDA_SDA") (pintype "bidirectional"))
    )
    (net (code "105") (name "unconnected-(U$1-PadSDA1)") (class "Default")
      (node (ref "U$1") (pin "SDA1") (pinfunction "SDA1_SDA1") (pintype "bidirectional"))
    )
    (net (code "106") (name "unconnected-(U$1-PadTX0)") (class "Default")
      (node (ref "U$1") (pin "TX0") (pinfunction "TX0_TX0") (pintype "bidirectional"))
    )
    (net (code "107") (name "unconnected-(U$1-PadTX3)") (class "Default")
      (node (ref "U$1") (pin "TX3") (pinfunction "TX3_TX3") (pintype "bidirectional"))
    )
    (net (code "108") (name "unconnected-(U2-3Y-Pad6)") (class "Default")
      (node (ref "U2") (pin "6") (pinfunction "3Y_6") (pintype "output"))
    )
    (net (code "109") (name "unconnected-(U2-4Y-Pad8)") (class "Default")
      (node (ref "U2") (pin "8") (pinfunction "4Y_8") (pintype "output"))
    )
    (net (code "110") (name "unconnected-(U2-5Y-Pad10)") (class "Default")
      (node (ref "U2") (pin "10") (pinfunction "5Y_10") (pintype "output"))
    )
    (net (code "111") (name "unconnected-(U2-6Y-Pad12)") (class "Default")
      (node (ref "U2") (pin "12") (pinfunction "6Y_12") (pintype "output"))
    )
    (net (code "112") (name "unconnected-(UM6-3.3V-PadP$13)") (class "Default")
      (node (ref "UM6") (pin "P$13") (pinfunction "3.3V_P$13") (pintype "bidirectional"))
    )
    (net (code "113") (name "unconnected-(UM6-D1-PadP$4)") (class "Default")
      (node (ref "UM6") (pin "P$4") (pinfunction "D1_P$4") (pintype "bidirectional"))
    )
    (net (code "114") (name "unconnected-(UM6-D2-PadP$5)") (class "Default")
      (node (ref "UM6") (pin "P$5") (pinfunction "D2_P$5") (pintype "bidirectional"))
    )
    (net (code "115") (name "unconnected-(UM6-D3-PadP$6)") (class "Default")
      (node (ref "UM6") (pin "P$6") (pinfunction "D3_P$6") (pintype "bidirectional"))
    )
    (net (code "116") (name "unconnected-(UM6-D4-PadP$7)") (class "Default")
      (node (ref "UM6") (pin "P$7") (pinfunction "D4_P$7") (pintype "bidirectional"))
    )
    (net (code "117") (name "unconnected-(UM6-D5-PadP$8)") (class "Default")
      (node (ref "UM6") (pin "P$8") (pinfunction "D5_P$8") (pintype "bidirectional"))
    )
    (net (code "118") (name "unconnected-(UM6-D6-PadP$9)") (class "Default")
      (node (ref "UM6") (pin "P$9") (pinfunction "D6_P$9") (pintype "bidirectional"))
    )
    (net (code "119") (name "unconnected-(UM6-GND2-PadP$12)") (class "Default")
      (node (ref "UM6") (pin "P$12") (pinfunction "GND2_P$12") (pintype "bidirectional"))
    )
    (net (code "120") (name "unconnected-(UM6-PGM-PadP$3)") (class "Default")
      (node (ref "UM6") (pin "P$3") (pinfunction "PGM_P$3") (pintype "bidirectional"))
    )
  )
)
